# PiOBD_CM4_CAN.net
KiCad netlist of a schematic drawn in Altium Designer
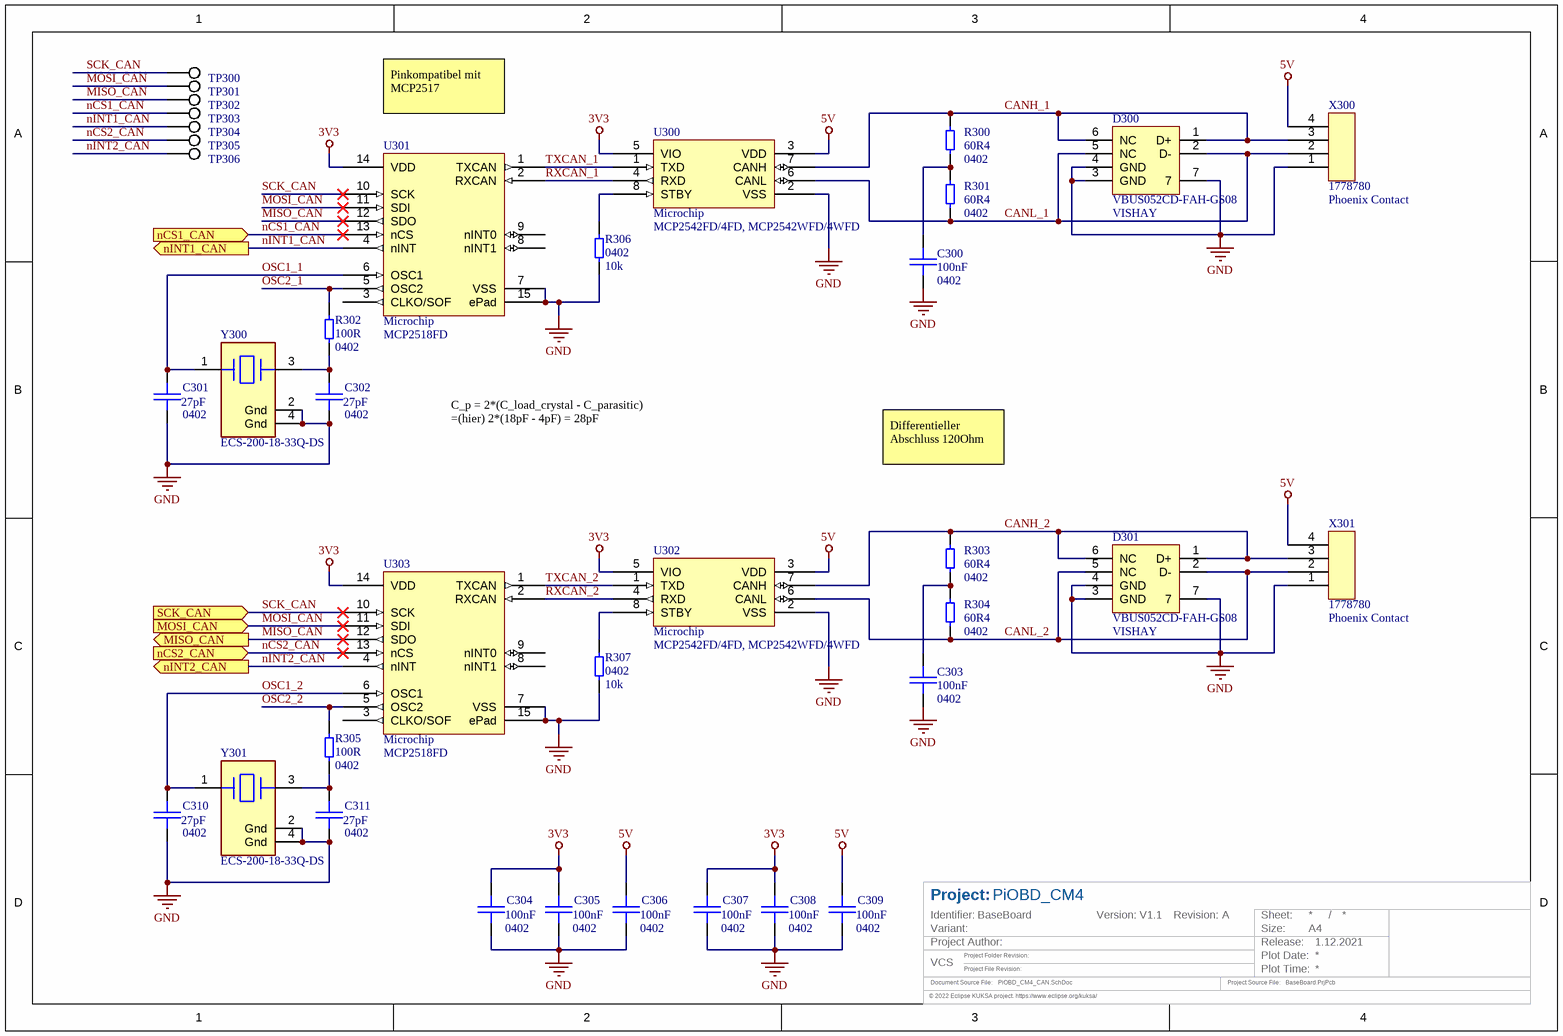
[diagram p0: PiOBD_CM4_CAN.SchDoc]

(export (version "E")
  (design (tool "Eeschema 10.0.6"))
  (components
    (comp (ref "C300")
      (value "CAP 0402 100n -10% +10% 6.3V X7R")
      (footprint "CAP 0402 [1005 Metric] X050 N")
      (description "SMD/SMT 0402 6.3V -10% +10% X7R - Multilayer Ceramic Capacitors MLCC")
      (fields
        (field (name "MANUFACTURER") "MURATA")
        (field (name "CAPACITANCE") "100nF")
        (field (name "MANUFACTURER PART NUMBER") "GRM155R70J104KA01#")
        (field (name "CASE") "0402")
      )
      (libsource (lib "ShareLib") (part "Capacitor non-polarized - Standard Schematic"))
    )
    (comp (ref "C301")
      (value "CAP 0402 27p -2% +2% 25V C0G")
      (footprint "CAP 0402 [1005 Metric] X050 N")
      (description "SMD/SMT 0402 25V -2% +2% C0G - Multilayer Ceramic Capacitors MLCC")
      (fields
        (field (name "MANUFACTURER") "MURATA")
        (field (name "CASE") "0402")
        (field (name "MANUFACTURER PART NUMBER") "GRM1555C1E270GA01#")
        (field (name "CAPACITANCE") "27pF")
      )
      (libsource (lib "ShareLib") (part "Capacitor non-polarized - Standard Schematic"))
    )
    (comp (ref "C302")
      (value "CAP 0402 27p -2% +2% 25V C0G")
      (footprint "CAP 0402 [1005 Metric] X050 N")
      (description "SMD/SMT 0402 25V -2% +2% C0G - Multilayer Ceramic Capacitors MLCC")
      (fields
        (field (name "MANUFACTURER") "MURATA")
        (field (name "CASE") "0402")
        (field (name "MANUFACTURER PART NUMBER") "GRM1555C1E270GA01#")
        (field (name "CAPACITANCE") "27pF")
      )
      (libsource (lib "ShareLib") (part "Capacitor non-polarized - Standard Schematic"))
    )
    (comp (ref "C303")
      (value "CAP 0402 100n -10% +10% 6.3V X7R")
      (footprint "CAP 0402 [1005 Metric] X050 N")
      (description "SMD/SMT 0402 6.3V -10% +10% X7R - Multilayer Ceramic Capacitors MLCC")
      (fields
        (field (name "MANUFACTURER") "MURATA")
        (field (name "CAPACITANCE") "100nF")
        (field (name "MANUFACTURER PART NUMBER") "GRM155R70J104KA01#")
        (field (name "CASE") "0402")
      )
      (libsource (lib "ShareLib") (part "Capacitor non-polarized - Standard Schematic"))
    )
    (comp (ref "C304")
      (value "CAP 0402 100n -10% +10% 6.3V X7R")
      (footprint "CAP 0402 [1005 Metric] X050 N")
      (description "SMD/SMT 0402 6.3V -10% +10% X7R - Multilayer Ceramic Capacitors MLCC")
      (fields
        (field (name "MANUFACTURER") "MURATA")
        (field (name "CAPACITANCE") "100nF")
        (field (name "MANUFACTURER PART NUMBER") "GRM155R70J104KA01#")
        (field (name "CASE") "0402")
      )
      (libsource (lib "ShareLib") (part "Capacitor non-polarized - Standard Schematic"))
    )
    (comp (ref "C305")
      (value "CAP 0402 100n -10% +10% 6.3V X7R")
      (footprint "CAP 0402 [1005 Metric] X050 N")
      (description "SMD/SMT 0402 6.3V -10% +10% X7R - Multilayer Ceramic Capacitors MLCC")
      (fields
        (field (name "MANUFACTURER") "MURATA")
        (field (name "CAPACITANCE") "100nF")
        (field (name "MANUFACTURER PART NUMBER") "GRM155R70J104KA01#")
        (field (name "CASE") "0402")
      )
      (libsource (lib "ShareLib") (part "Capacitor non-polarized - Standard Schematic"))
    )
    (comp (ref "C306")
      (value "CAP 0402 100n -10% +10% 6.3V X7R")
      (footprint "CAP 0402 [1005 Metric] X050 N")
      (description "SMD/SMT 0402 6.3V -10% +10% X7R - Multilayer Ceramic Capacitors MLCC")
      (fields
        (field (name "MANUFACTURER") "MURATA")
        (field (name "CAPACITANCE") "100nF")
        (field (name "MANUFACTURER PART NUMBER") "GRM155R70J104KA01#")
        (field (name "CASE") "0402")
      )
      (libsource (lib "ShareLib") (part "Capacitor non-polarized - Standard Schematic"))
    )
    (comp (ref "C307")
      (value "CAP 0402 100n -10% +10% 6.3V X7R")
      (footprint "CAP 0402 [1005 Metric] X050 N")
      (description "SMD/SMT 0402 6.3V -10% +10% X7R - Multilayer Ceramic Capacitors MLCC")
      (fields
        (field (name "MANUFACTURER") "MURATA")
        (field (name "CAPACITANCE") "100nF")
        (field (name "MANUFACTURER PART NUMBER") "GRM155R70J104KA01#")
        (field (name "CASE") "0402")
      )
      (libsource (lib "ShareLib") (part "Capacitor non-polarized - Standard Schematic"))
    )
    (comp (ref "C308")
      (value "CAP 0402 100n -10% +10% 6.3V X7R")
      (footprint "CAP 0402 [1005 Metric] X050 N")
      (description "SMD/SMT 0402 6.3V -10% +10% X7R - Multilayer Ceramic Capacitors MLCC")
      (fields
        (field (name "MANUFACTURER") "MURATA")
        (field (name "CAPACITANCE") "100nF")
        (field (name "MANUFACTURER PART NUMBER") "GRM155R70J104KA01#")
        (field (name "CASE") "0402")
      )
      (libsource (lib "ShareLib") (part "Capacitor non-polarized - Standard Schematic"))
    )
    (comp (ref "C309")
      (value "CAP 0402 100n -10% +10% 6.3V X7R")
      (footprint "CAP 0402 [1005 Metric] X050 N")
      (description "SMD/SMT 0402 6.3V -10% +10% X7R - Multilayer Ceramic Capacitors MLCC")
      (fields
        (field (name "MANUFACTURER") "MURATA")
        (field (name "CAPACITANCE") "100nF")
        (field (name "MANUFACTURER PART NUMBER") "GRM155R70J104KA01#")
        (field (name "CASE") "0402")
      )
      (libsource (lib "ShareLib") (part "Capacitor non-polarized - Standard Schematic"))
    )
    (comp (ref "C310")
      (value "CAP 0402 27p -2% +2% 25V C0G")
      (footprint "CAP 0402 [1005 Metric] X050 N")
      (description "SMD/SMT 0402 25V -2% +2% C0G - Multilayer Ceramic Capacitors MLCC")
      (fields
        (field (name "MANUFACTURER") "MURATA")
        (field (name "CASE") "0402")
        (field (name "MANUFACTURER PART NUMBER") "GRM1555C1E270GA01#")
        (field (name "CAPACITANCE") "27pF")
      )
      (libsource (lib "ShareLib") (part "Capacitor non-polarized - Standard Schematic"))
    )
    (comp (ref "C311")
      (value "CAP 0402 27p -2% +2% 25V C0G")
      (footprint "CAP 0402 [1005 Metric] X050 N")
      (description "SMD/SMT 0402 25V -2% +2% C0G - Multilayer Ceramic Capacitors MLCC")
      (fields
        (field (name "MANUFACTURER") "MURATA")
        (field (name "CASE") "0402")
        (field (name "MANUFACTURER PART NUMBER") "GRM1555C1E270GA01#")
        (field (name "CAPACITANCE") "27pF")
      )
      (libsource (lib "ShareLib") (part "Capacitor non-polarized - Standard Schematic"))
    )
    (comp (ref "D300")
      (value "VISHAY - VBUS052CD-FAH-GS08")
      (footprint "VISHAY - VBUS052CD-FAH")
      (description "2-Line BUS-Port ESD-Protection - Flow Through Design")
      (fields
        (field (name "MANUFACTURER PART NUMBER") "VBUS052CD-FAH-GS08")
        (field (name "MANUFACTURER") "VISHAY")
      )
      (libsource (lib "ShareLib") (part "VISHAY - VBUS052CD-FAH"))
    )
    (comp (ref "D301")
      (value "VISHAY - VBUS052CD-FAH-GS08")
      (footprint "VISHAY - VBUS052CD-FAH")
      (description "2-Line BUS-Port ESD-Protection - Flow Through Design")
      (fields
        (field (name "MANUFACTURER PART NUMBER") "VBUS052CD-FAH-GS08")
        (field (name "MANUFACTURER") "VISHAY")
      )
      (libsource (lib "ShareLib") (part "VISHAY - VBUS052CD-FAH"))
    )
    (comp (ref "R300")
      (value "RES 0402 60R4 1% 0W0625")
      (footprint "RES 0402 [1005 Metric]_N")
      (description "RC0402 series chip resistor with lead-free terminations made by thick film process")
      (fields
        (field (name "RESISTANCE") "60R4")
        (field (name "MANUFACTURER PART NUMBER") "RC0402FR-0760R4L")
        (field (name "MANUFACTURER") "YAGEO")
        (field (name "CASE") "0402")
      )
      (libsource (lib "ShareLib") (part "Standard Schematic - Resistor Universal"))
    )
    (comp (ref "R301")
      (value "RES 0402 60R4 1% 0W0625")
      (footprint "RES 0402 [1005 Metric]_N")
      (description "RC0402 series chip resistor with lead-free terminations made by thick film process")
      (fields
        (field (name "RESISTANCE") "60R4")
        (field (name "MANUFACTURER PART NUMBER") "RC0402FR-0760R4L")
        (field (name "MANUFACTURER") "YAGEO")
        (field (name "CASE") "0402")
      )
      (libsource (lib "ShareLib") (part "Standard Schematic - Resistor Universal"))
    )
    (comp (ref "R302")
      (value "RES 0402 100R 1% 63mW")
      (footprint "RES 0402 [1005 Metric]_N")
      (description "RC0402 series chip resistor with lead-free terminations made by thick film process")
      (fields
        (field (name "RESISTANCE") "100R")
        (field (name "CASE") "0402")
        (field (name "MANUFACTURER") "ROHM")
        (field (name "MANUFACTURER PART NUMBER") "MCR01MZPF100")
      )
      (libsource (lib "ShareLib") (part "Standard Schematic - Resistor Universal"))
    )
    (comp (ref "R303")
      (value "RES 0402 60R4 1% 0W0625")
      (footprint "RES 0402 [1005 Metric]_N")
      (description "RC0402 series chip resistor with lead-free terminations made by thick film process")
      (fields
        (field (name "RESISTANCE") "60R4")
        (field (name "MANUFACTURER PART NUMBER") "RC0402FR-0760R4L")
        (field (name "MANUFACTURER") "YAGEO")
        (field (name "CASE") "0402")
      )
      (libsource (lib "ShareLib") (part "Standard Schematic - Resistor Universal"))
    )
    (comp (ref "R304")
      (value "RES 0402 60R4 1% 0W0625")
      (footprint "RES 0402 [1005 Metric]_N")
      (description "RC0402 series chip resistor with lead-free terminations made by thick film process")
      (fields
        (field (name "RESISTANCE") "60R4")
        (field (name "MANUFACTURER PART NUMBER") "RC0402FR-0760R4L")
        (field (name "MANUFACTURER") "YAGEO")
        (field (name "CASE") "0402")
      )
      (libsource (lib "ShareLib") (part "Standard Schematic - Resistor Universal"))
    )
    (comp (ref "R305")
      (value "RES 0402 100R 1% 63mW")
      (footprint "RES 0402 [1005 Metric]_N")
      (description "RC0402 series chip resistor with lead-free terminations made by thick film process")
      (fields
        (field (name "RESISTANCE") "100R")
        (field (name "CASE") "0402")
        (field (name "MANUFACTURER") "ROHM")
        (field (name "MANUFACTURER PART NUMBER") "MCR01MZPF100")
      )
      (libsource (lib "ShareLib") (part "Standard Schematic - Resistor Universal"))
    )
    (comp (ref "R306")
      (value "RES 0402 10K 1% 0W0625")
      (footprint "RES 0402 [1005 Metric]_N")
      (description "RC0402 series chip resistor with lead-free terminations made by thick film process")
      (fields
        (field (name "MANUFACTURER PART NUMBER") "RC0402FR-0710KL")
        (field (name "CASE") "0402")
        (field (name "MANUFACTURER") "YAGEO")
        (field (name "RESISTANCE") "10k")
      )
      (libsource (lib "ShareLib") (part "Standard Schematic - Resistor Universal"))
    )
    (comp (ref "R307")
      (value "RES 0402 10K 1% 0W0625")
      (footprint "RES 0402 [1005 Metric]_N")
      (description "RC0402 series chip resistor with lead-free terminations made by thick film process")
      (fields
        (field (name "MANUFACTURER PART NUMBER") "RC0402FR-0710KL")
        (field (name "CASE") "0402")
        (field (name "MANUFACTURER") "YAGEO")
        (field (name "RESISTANCE") "10k")
      )
      (libsource (lib "ShareLib") (part "Standard Schematic - Resistor Universal"))
    )
    (comp (ref "TP300")
      (value "Testpad, 0.8mm x 0.8mm, round")
      (footprint "Testpad, 0.8mm x 0.8mm, round")
      (libsource (lib "ShareLib") (part "Testpoint (No BOM)"))
    )
    (comp (ref "TP301")
      (value "Testpad, 0.8mm x 0.8mm, round")
      (footprint "Testpad, 0.8mm x 0.8mm, round")
      (libsource (lib "ShareLib") (part "Testpoint (No BOM)"))
    )
    (comp (ref "TP302")
      (value "Testpad, 0.8mm x 0.8mm, round")
      (footprint "Testpad, 0.8mm x 0.8mm, round")
      (libsource (lib "ShareLib") (part "Testpoint (No BOM)"))
    )
    (comp (ref "TP303")
      (value "Testpad, 0.8mm x 0.8mm, round")
      (footprint "Testpad, 0.8mm x 0.8mm, round")
      (libsource (lib "ShareLib") (part "Testpoint (No BOM)"))
    )
    (comp (ref "TP304")
      (value "Testpad, 0.8mm x 0.8mm, round")
      (footprint "Testpad, 0.8mm x 0.8mm, round")
      (libsource (lib "ShareLib") (part "Testpoint (No BOM)"))
    )
    (comp (ref "TP305")
      (value "Testpad, 0.8mm x 0.8mm, round")
      (footprint "Testpad, 0.8mm x 0.8mm, round")
      (libsource (lib "ShareLib") (part "Testpoint (No BOM)"))
    )
    (comp (ref "TP306")
      (value "Testpad, 0.8mm x 0.8mm, round")
      (footprint "Testpad, 0.8mm x 0.8mm, round")
      (libsource (lib "ShareLib") (part "Testpoint (No BOM)"))
    )
    (comp (ref "U300")
      (value "MICROCHIP - MCP2542FD/4FD")
      (footprint "SOIC127P600X175-8N")
      (description "CAN FD Transceiver with Wake-up Pattern (WUP) Option")
      (fields
        (field (name "MANUFACTURER") "Microchip")
        (field (name "MANUFACTURER PART NUMBER") "MCP2542FD/4FD, MCP2542WFD/4WFD")
      )
      (libsource (lib "ShareLib") (part "MICROCHIP - MCP2542FD_4FD"))
    )
    (comp (ref "U301")
      (value "MICROCHIP - MCP2518FD")
      (footprint "SON65P300X90_HS-15N")
      (description "CAN FD Controller with SPI Interface")
      (fields (field (name "MANUFACTURER") "Microchip") (field (name "MANUFACTURER PART NUMBER") "MCP2518FD"))
      (libsource (lib "ShareLib") (part "Microchip - MCP2518FD"))
    )
    (comp (ref "U302")
      (value "MICROCHIP - MCP2542FD/4FD")
      (footprint "SOIC127P600X175-8N")
      (description "CAN FD Transceiver with Wake-up Pattern (WUP) Option")
      (fields
        (field (name "MANUFACTURER") "Microchip")
        (field (name "MANUFACTURER PART NUMBER") "MCP2542FD/4FD, MCP2542WFD/4WFD")
      )
      (libsource (lib "ShareLib") (part "MICROCHIP - MCP2542FD_4FD"))
    )
    (comp (ref "U303")
      (value "MICROCHIP - MCP2518FD")
      (footprint "SON65P300X90_HS-15N")
      (description "CAN FD Controller with SPI Interface")
      (fields (field (name "MANUFACTURER") "Microchip") (field (name "MANUFACTURER PART NUMBER") "MCP2518FD"))
      (libsource (lib "ShareLib") (part "Microchip - MCP2518FD"))
    )
    (comp (ref "X300")
      (value "PHOENIX CONTACT - PTSM 0,5/ 4-HH-2,5-SMD R32")
      (footprint "PHOENIX CONTACT - PTSM 0,5_ 4-HH-2,5-SMD R32-Footprint-1")
      (description "Leiterplatten-Grundleiste - PTSM 0,5/ 4-HH-2,5-SMD R32")
      (fields
        (field (name "MANUFACTURER PART NUMBER") "1778780")
        (field (name "MANUFACTURER") "Phoenix Contact")
      )
      (libsource (lib "ShareLib") (part "PHOENIX CONTACT - PTSM 0,5_ 4-HH-2,5-SMD R32"))
    )
    (comp (ref "X301")
      (value "PHOENIX CONTACT - PTSM 0,5/ 4-HH-2,5-SMD R32")
      (footprint "PHOENIX CONTACT - PTSM 0,5_ 4-HH-2,5-SMD R32-Footprint-1")
      (description "Leiterplatten-Grundleiste - PTSM 0,5/ 4-HH-2,5-SMD R32")
      (fields
        (field (name "MANUFACTURER PART NUMBER") "1778780")
        (field (name "MANUFACTURER") "Phoenix Contact")
      )
      (libsource (lib "ShareLib") (part "PHOENIX CONTACT - PTSM 0,5_ 4-HH-2,5-SMD R32"))
    )
    (comp (ref "Y300")
      (value "ECS-200-18-33Q-DS")
      (footprint "FP-ECX-33Q-MFG")
      (description "CRYSTAL 20.0000MHZ 18PF SMD")
      (fields
        (field (name "OCTOPART") "https://octopart.com/ecs-200-18-33q-ds-ecs+international-29290571")
        (field (name "TOLERANCE") "30ppm")
      )
      (libsource (lib "Altium Content Vault") (part "2e3fdc1e60336f3f4c57fc5a79d902f"))
    )
    (comp (ref "Y301")
      (value "ECS-200-18-33Q-DS")
      (footprint "FP-ECX-33Q-MFG")
      (description "CRYSTAL 20.0000MHZ 18PF SMD")
      (fields
        (field (name "OCTOPART") "https://octopart.com/ecs-200-18-33q-ds-ecs+international-29290571")
        (field (name "TOLERANCE") "30ppm")
      )
      (libsource (lib "Altium Content Vault") (part "2e3fdc1e60336f3f4c57fc5a79d902f"))
    )
  )
  (nets
    (net (code "1") (name "/CANH_1") (class "Default")
      (node (ref "D300") (pin "1") (pinfunction "D+_1") (pintype "passive"))
      (node (ref "D300") (pin "6") (pinfunction "NC_6") (pintype "passive"))
      (node (ref "R300") (pin "2") (pinfunction "2_2") (pintype "passive"))
      (node (ref "U300") (pin "7") (pinfunction "CANH_7") (pintype "bidirectional"))
      (node (ref "X300") (pin "3") (pintype "passive"))
    )
    (net (code "2") (name "/CANH_2") (class "Default")
      (node (ref "D301") (pin "1") (pinfunction "D+_1") (pintype "passive"))
      (node (ref "D301") (pin "6") (pinfunction "NC_6") (pintype "passive"))
      (node (ref "R303") (pin "2") (pinfunction "2_2") (pintype "passive"))
      (node (ref "U302") (pin "7") (pinfunction "CANH_7") (pintype "bidirectional"))
      (node (ref "X301") (pin "3") (pintype "passive"))
    )
    (net (code "3") (name "/CANL_1") (class "Default")
      (node (ref "D300") (pin "2") (pinfunction "D-_2") (pintype "passive"))
      (node (ref "D300") (pin "5") (pinfunction "NC_5") (pintype "passive"))
      (node (ref "R301") (pin "1") (pinfunction "1_1") (pintype "passive"))
      (node (ref "U300") (pin "6") (pinfunction "CANL_6") (pintype "bidirectional"))
      (node (ref "X300") (pin "2") (pintype "passive"))
    )
    (net (code "4") (name "/CANL_2") (class "Default")
      (node (ref "D301") (pin "2") (pinfunction "D-_2") (pintype "passive"))
      (node (ref "D301") (pin "5") (pinfunction "NC_5") (pintype "passive"))
      (node (ref "R304") (pin "1") (pinfunction "1_1") (pintype "passive"))
      (node (ref "U302") (pin "6") (pinfunction "CANL_6") (pintype "bidirectional"))
      (node (ref "X301") (pin "2") (pintype "passive"))
    )
    (net (code "5") (name "/MISO_CAN") (class "Default")
      (node (ref "TP302") (pin "1") (pinfunction "1_1") (pintype "passive"))
      (node (ref "U301") (pin "12") (pinfunction "SDO_12") (pintype "output"))
      (node (ref "U303") (pin "12") (pinfunction "SDO_12") (pintype "output"))
    )
    (net (code "6") (name "/MOSI_CAN") (class "Default")
      (node (ref "TP301") (pin "1") (pinfunction "1_1") (pintype "passive"))
      (node (ref "U301") (pin "11") (pinfunction "SDI_11") (pintype "input"))
      (node (ref "U303") (pin "11") (pinfunction "SDI_11") (pintype "input"))
    )
    (net (code "7") (name "/OSC1_1") (class "Default")
      (node (ref "C301") (pin "2") (pinfunction "2_2") (pintype "passive"))
      (node (ref "U301") (pin "6") (pinfunction "OSC1_6") (pintype "input"))
      (node (ref "Y300") (pin "1") (pinfunction "In/Out_1") (pintype "passive"))
    )
    (net (code "8") (name "/OSC1_2") (class "Default")
      (node (ref "C310") (pin "2") (pinfunction "2_2") (pintype "passive"))
      (node (ref "U303") (pin "6") (pinfunction "OSC1_6") (pintype "input"))
      (node (ref "Y301") (pin "1") (pinfunction "In/Out_1") (pintype "passive"))
    )
    (net (code "9") (name "/OSC2_1") (class "Default")
      (node (ref "R302") (pin "2") (pinfunction "2_2") (pintype "passive"))
      (node (ref "U301") (pin "5") (pinfunction "OSC2_5") (pintype "output"))
    )
    (net (code "10") (name "/OSC2_2") (class "Default")
      (node (ref "R305") (pin "2") (pinfunction "2_2") (pintype "passive"))
      (node (ref "U303") (pin "5") (pinfunction "OSC2_5") (pintype "output"))
    )
    (net (code "11") (name "/RXCAN_1") (class "Default")
      (node (ref "U300") (pin "4") (pinfunction "RXD_4") (pintype "output"))
      (node (ref "U301") (pin "2") (pinfunction "RXCAN_2") (pintype "input"))
    )
    (net (code "12") (name "/RXCAN_2") (class "Default")
      (node (ref "U302") (pin "4") (pinfunction "RXD_4") (pintype "output"))
      (node (ref "U303") (pin "2") (pinfunction "RXCAN_2") (pintype "input"))
    )
    (net (code "13") (name "/SCK_CAN") (class "Default")
      (node (ref "TP300") (pin "1") (pinfunction "1_1") (pintype "passive"))
      (node (ref "U301") (pin "10") (pinfunction "SCK_10") (pintype "input"))
      (node (ref "U303") (pin "10") (pinfunction "SCK_10") (pintype "input"))
    )
    (net (code "14") (name "/TXCAN_1") (class "Default")
      (node (ref "U300") (pin "1") (pinfunction "TXD_1") (pintype "input"))
      (node (ref "U301") (pin "1") (pinfunction "TXCAN_1") (pintype "output"))
    )
    (net (code "15") (name "/TXCAN_2") (class "Default")
      (node (ref "U302") (pin "1") (pinfunction "TXD_1") (pintype "input"))
      (node (ref "U303") (pin "1") (pinfunction "TXCAN_1") (pintype "output"))
    )
    (net (code "16") (name "/nCS1_CAN") (class "Default")
      (node (ref "TP303") (pin "1") (pinfunction "1_1") (pintype "passive"))
      (node (ref "U301") (pin "13") (pinfunction "nCS_13") (pintype "input"))
    )
    (net (code "17") (name "/nCS2_CAN") (class "Default")
      (node (ref "TP305") (pin "1") (pinfunction "1_1") (pintype "passive"))
      (node (ref "U303") (pin "13") (pinfunction "nCS_13") (pintype "input"))
    )
    (net (code "18") (name "/nINT1_CAN") (class "Default")
      (node (ref "TP304") (pin "1") (pinfunction "1_1") (pintype "passive"))
      (node (ref "U301") (pin "4") (pinfunction "nINT_4") (pintype "output"))
    )
    (net (code "19") (name "/nINT2_CAN") (class "Default")
      (node (ref "TP306") (pin "1") (pinfunction "1_1") (pintype "passive"))
      (node (ref "U303") (pin "4") (pinfunction "nINT_4") (pintype "output"))
    )
    (net (code "20") (name "3V3") (class "Default")
      (node (ref "C304") (pin "2") (pinfunction "2_2") (pintype "passive"))
      (node (ref "C305") (pin "2") (pinfunction "2_2") (pintype "passive"))
      (node (ref "C307") (pin "2") (pinfunction "2_2") (pintype "passive"))
      (node (ref "C308") (pin "2") (pinfunction "2_2") (pintype "passive"))
      (node (ref "U300") (pin "5") (pinfunction "VIO_5") (pintype "power_in"))
      (node (ref "U301") (pin "14") (pinfunction "VDD_14") (pintype "power_in"))
      (node (ref "U302") (pin "5") (pinfunction "VIO_5") (pintype "power_in"))
      (node (ref "U303") (pin "14") (pinfunction "VDD_14") (pintype "power_in"))
    )
    (net (code "21") (name "5V") (class "Default")
      (node (ref "C306") (pin "2") (pinfunction "2_2") (pintype "passive"))
      (node (ref "C309") (pin "2") (pinfunction "2_2") (pintype "passive"))
      (node (ref "U300") (pin "3") (pinfunction "VDD_3") (pintype "power_in"))
      (node (ref "U302") (pin "3") (pinfunction "VDD_3") (pintype "power_in"))
      (node (ref "X300") (pin "4") (pintype "passive"))
      (node (ref "X301") (pin "4") (pintype "passive"))
    )
    (net (code "22") (name "GND") (class "Default")
      (node (ref "C300") (pin "2") (pinfunction "2_2") (pintype "passive"))
      (node (ref "C301") (pin "1") (pinfunction "1_1") (pintype "passive"))
      (node (ref "C302") (pin "1") (pinfunction "1_1") (pintype "passive"))
      (node (ref "C303") (pin "2") (pinfunction "2_2") (pintype "passive"))
      (node (ref "C304") (pin "1") (pinfunction "1_1") (pintype "passive"))
      (node (ref "C305") (pin "1") (pinfunction "1_1") (pintype "passive"))
      (node (ref "C306") (pin "1") (pinfunction "1_1") (pintype "passive"))
      (node (ref "C307") (pin "1") (pinfunction "1_1") (pintype "passive"))
      (node (ref "C308") (pin "1") (pinfunction "1_1") (pintype "passive"))
      (node (ref "C309") (pin "1") (pinfunction "1_1") (pintype "passive"))
      (node (ref "C310") (pin "1") (pinfunction "1_1") (pintype "passive"))
      (node (ref "C311") (pin "1") (pinfunction "1_1") (pintype "passive"))
      (node (ref "D300") (pin "3") (pinfunction "GND_3") (pintype "power_in"))
      (node (ref "D300") (pin "4") (pinfunction "GND_4") (pintype "power_in"))
      (node (ref "D300") (pin "7") (pinfunction "7_7") (pintype "passive"))
      (node (ref "D301") (pin "3") (pinfunction "GND_3") (pintype "power_in"))
      (node (ref "D301") (pin "4") (pinfunction "GND_4") (pintype "power_in"))
      (node (ref "D301") (pin "7") (pinfunction "7_7") (pintype "passive"))
      (node (ref "R306") (pin "2") (pinfunction "2_2") (pintype "passive"))
      (node (ref "R307") (pin "2") (pinfunction "2_2") (pintype "passive"))
      (node (ref "U300") (pin "2") (pinfunction "VSS_2") (pintype "power_in"))
      (node (ref "U301") (pin "15") (pinfunction "ePad_15") (pintype "power_in"))
      (node (ref "U301") (pin "7") (pinfunction "VSS_7") (pintype "power_in"))
      (node (ref "U302") (pin "2") (pinfunction "VSS_2") (pintype "power_in"))
      (node (ref "U303") (pin "15") (pinfunction "ePad_15") (pintype "power_in"))
      (node (ref "U303") (pin "7") (pinfunction "VSS_7") (pintype "power_in"))
      (node (ref "X300") (pin "1") (pintype "passive"))
      (node (ref "X301") (pin "1") (pintype "passive"))
      (node (ref "Y300") (pin "2") (pinfunction "Gnd_2") (pintype "power_in"))
      (node (ref "Y300") (pin "4") (pinfunction "Gnd_4") (pintype "power_in"))
      (node (ref "Y301") (pin "2") (pinfunction "Gnd_2") (pintype "power_in"))
      (node (ref "Y301") (pin "4") (pinfunction "Gnd_4") (pintype "power_in"))
    )
    (net (code "23") (name "Net-(C300-Pad1)") (class "Default")
      (node (ref "C300") (pin "1") (pinfunction "1_1") (pintype "passive"))
      (node (ref "R300") (pin "1") (pinfunction "1_1") (pintype "passive"))
      (node (ref "R301") (pin "2") (pinfunction "2_2") (pintype "passive"))
    )
    (net (code "24") (name "Net-(C303-Pad1)") (class "Default")
      (node (ref "C303") (pin "1") (pinfunction "1_1") (pintype "passive"))
      (node (ref "R303") (pin "1") (pinfunction "1_1") (pintype "passive"))
      (node (ref "R304") (pin "2") (pinfunction "2_2") (pintype "passive"))
    )
    (net (code "25") (name "Net-(U300-STBY)") (class "Default")
      (node (ref "R306") (pin "1") (pinfunction "1_1") (pintype "passive"))
      (node (ref "U300") (pin "8") (pinfunction "STBY_8") (pintype "input"))
    )
    (net (code "26") (name "Net-(U302-STBY)") (class "Default")
      (node (ref "R307") (pin "1") (pinfunction "1_1") (pintype "passive"))
      (node (ref "U302") (pin "8") (pinfunction "STBY_8") (pintype "input"))
    )
    (net (code "27") (name "Net-(Y300-Out{slash}In)") (class "Default")
      (node (ref "C302") (pin "2") (pinfunction "2_2") (pintype "passive"))
      (node (ref "R302") (pin "1") (pinfunction "1_1") (pintype "passive"))
      (node (ref "Y300") (pin "3") (pinfunction "Out/In_3") (pintype "passive"))
    )
    (net (code "28") (name "Net-(Y301-Out{slash}In)") (class "Default")
      (node (ref "C311") (pin "2") (pinfunction "2_2") (pintype "passive"))
      (node (ref "R305") (pin "1") (pinfunction "1_1") (pintype "passive"))
      (node (ref "Y301") (pin "3") (pinfunction "Out/In_3") (pintype "passive"))
    )
    (net (code "29") (name "unconnected-(U301-CLKO{slash}SOF-Pad3)") (class "Default")
      (node (ref "U301") (pin "3") (pinfunction "CLKO/SOF_3") (pintype "output"))
    )
    (net (code "30") (name "unconnected-(U301-nINT0-Pad9)") (class "Default")
      (node (ref "U301") (pin "9") (pinfunction "nINT0_9") (pintype "bidirectional"))
    )
    (net (code "31") (name "unconnected-(U301-nINT1-Pad8)") (class "Default")
      (node (ref "U301") (pin "8") (pinfunction "nINT1_8") (pintype "bidirectional"))
    )
    (net (code "32") (name "unconnected-(U303-CLKO{slash}SOF-Pad3)") (class "Default")
      (node (ref "U303") (pin "3") (pinfunction "CLKO/SOF_3") (pintype "output"))
    )
    (net (code "33") (name "unconnected-(U303-nINT0-Pad9)") (class "Default")
      (node (ref "U303") (pin "9") (pinfunction "nINT0_9") (pintype "bidirectional"))
    )
    (net (code "34") (name "unconnected-(U303-nINT1-Pad8)") (class "Default")
      (node (ref "U303") (pin "8") (pinfunction "nINT1_8") (pintype "bidirectional"))
    )
  )
)
